# Programmer.net
KiCad netlist of a schematic drawn in Altium Designer
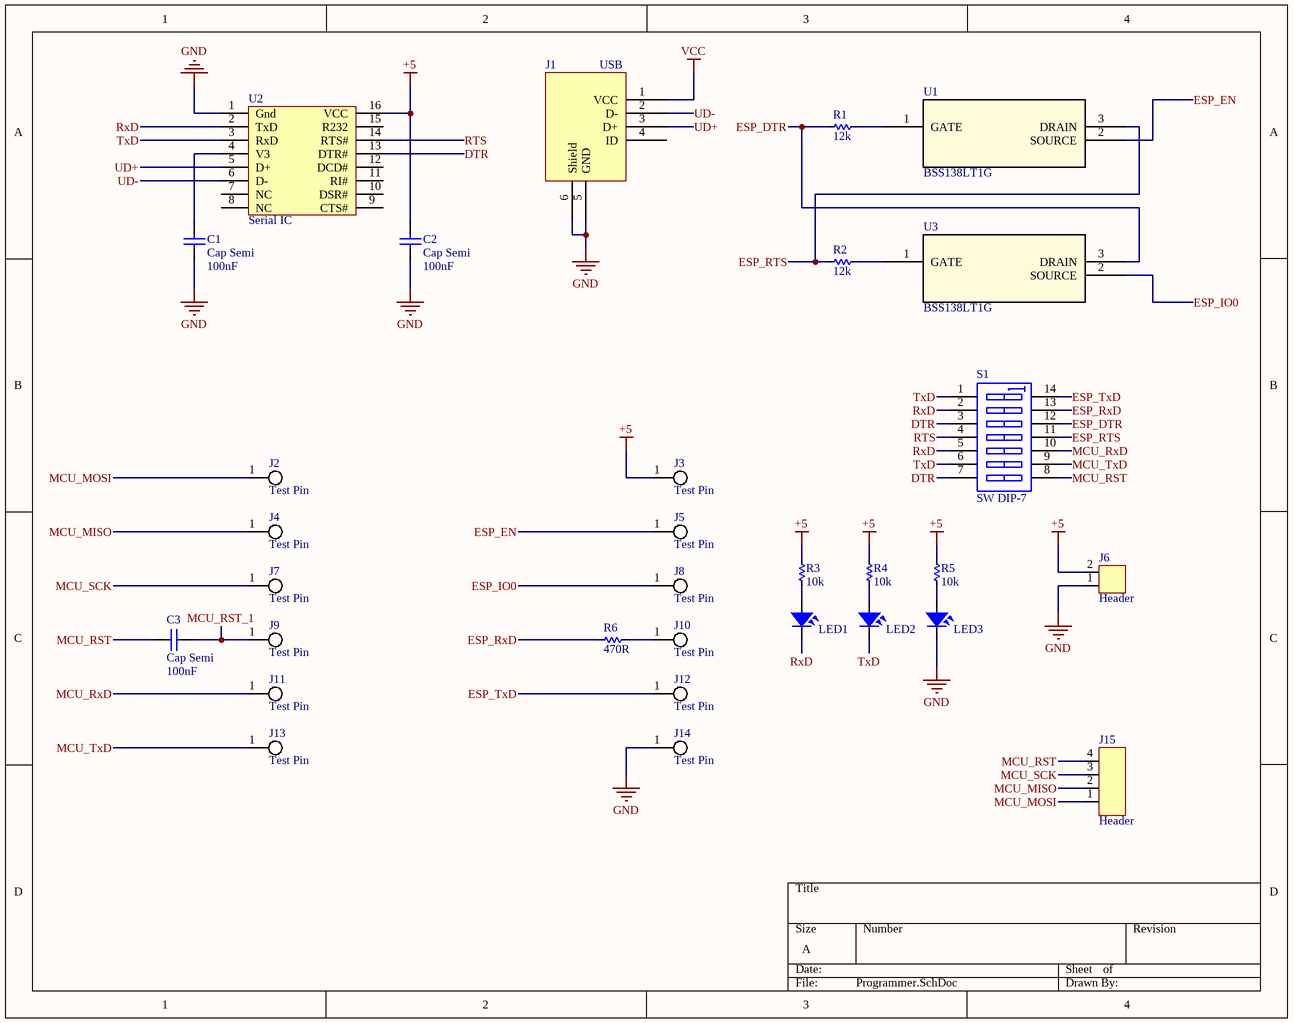
[diagram p0: Programmer.SchDoc]

(export (version "E")
  (design (tool "Eeschema 10.0.6"))
  (components
    (comp (ref "C1")
      (value "Cap Semi")
      (footprint "1608[0603]")
      (description "Capacitor (Semiconductor SIM Model)")
      (fields (field (name "ALTIUM_VALUE") "100nF") (field (name "PUBLISHER") "Altium Limited"))
      (libsource (lib "Miscellaneous Devices") (part "Cap Semi"))
    )
    (comp (ref "C2")
      (value "Cap Semi")
      (footprint "1608[0603]")
      (description "Capacitor (Semiconductor SIM Model)")
      (fields (field (name "ALTIUM_VALUE") "100nF") (field (name "PUBLISHER") "Altium Limited"))
      (libsource (lib "Miscellaneous Devices") (part "Cap Semi"))
    )
    (comp (ref "C3")
      (value "Cap Semi")
      (footprint "1608[0603]")
      (description "Capacitor (Semiconductor SIM Model)")
      (fields (field (name "ALTIUM_VALUE") "100nF") (field (name "PUBLISHER") "Altium Limited"))
      (libsource (lib "Miscellaneous Devices") (part "Cap Semi"))
    )
    (comp (ref "J1")
      (value "USB")
      (footprint "USB-MICRO-B-1")
      (description "MicroUSB 5pin TypeB SMD")
      (libsource (lib "MyLibrary-001") (part "USB-Micro-B_1"))
    )
    (comp (ref "J2") (value "Test Pin") (footprint "P50-J1") (libsource (lib "TestPin") (part "P50-J1")))
    (comp (ref "J3") (value "Test Pin") (footprint "P50-J1") (libsource (lib "TestPin") (part "P50-J1")))
    (comp (ref "J4") (value "Test Pin") (footprint "P50-J1") (libsource (lib "TestPin") (part "P50-J1")))
    (comp (ref "J5") (value "Test Pin") (footprint "P50-J1") (libsource (lib "TestPin") (part "P50-J1")))
    (comp (ref "J6")
      (value "Header")
      (footprint "Header 1x2 Pin 2.54mm")
      (description "Header 1x2Pin 2.54mm")
      (libsource (lib "MyLibrary-001") (part "Header 1x2Pin 2.54mm"))
    )
    (comp (ref "J7") (value "Test Pin") (footprint "P50-J1") (libsource (lib "TestPin") (part "P50-J1")))
    (comp (ref "J8") (value "Test Pin") (footprint "P50-J1") (libsource (lib "TestPin") (part "P50-J1")))
    (comp (ref "J9") (value "Test Pin") (footprint "P50-J1") (libsource (lib "TestPin") (part "P50-J1")))
    (comp (ref "J10") (value "Test Pin") (footprint "P50-J1") (libsource (lib "TestPin") (part "P50-J1")))
    (comp (ref "J11") (value "Test Pin") (footprint "P50-J1") (libsource (lib "TestPin") (part "P50-J1")))
    (comp (ref "J12") (value "Test Pin") (footprint "P50-J1") (libsource (lib "TestPin") (part "P50-J1")))
    (comp (ref "J13") (value "Test Pin") (footprint "P50-J1") (libsource (lib "TestPin") (part "P50-J1")))
    (comp (ref "J14") (value "Test Pin") (footprint "P50-J1") (libsource (lib "TestPin") (part "P50-J1")))
    (comp (ref "J15")
      (value "Header")
      (footprint "HEADER 1X4PIN 2.54mm")
      (description "Header 1x4Pin 2.54mm")
      (libsource (lib "MyLibrary-001") (part "Header 1x4Pin 2.54mm"))
    )
    (comp (ref "LED1") (value "LED") (footprint "LED-0805-Red") (libsource (lib "LIBRARY") (part "LED SMD")))
    (comp (ref "LED2") (value "LED") (footprint "LED-0805-Red") (libsource (lib "LIBRARY") (part "LED SMD")))
    (comp (ref "LED3") (value "LED") (footprint "LED-0805-Red") (libsource (lib "LIBRARY") (part "LED SMD")))
    (comp (ref "R1")
      (value "12k")
      (footprint "RES-SMD-0603")
      (description "Resistor")
      (fields
        (field (name "MANUFACTURER") "Generic Components")
        (field (name "Comment") "Res")
        (field (name "PUBLISHER") "Altium Hobart Technology Centre")
      )
      (libsource (lib "LIBRARY") (part "Res-SMD"))
    )
    (comp (ref "R2")
      (value "12k")
      (footprint "RES-SMD-0603")
      (description "Resistor")
      (fields
        (field (name "MANUFACTURER") "Generic Components")
        (field (name "Comment") "Res")
        (field (name "PUBLISHER") "Altium Hobart Technology Centre")
      )
      (libsource (lib "LIBRARY") (part "Res-SMD"))
    )
    (comp (ref "R3")
      (value "10k")
      (footprint "RES-SMD-0603")
      (description "Resistor")
      (fields
        (field (name "MANUFACTURER") "Generic Components")
        (field (name "Comment") "Res")
        (field (name "PUBLISHER") "Altium Hobart Technology Centre")
      )
      (libsource (lib "LIBRARY") (part "Res-SMD"))
    )
    (comp (ref "R4")
      (value "10k")
      (footprint "RES-SMD-0603")
      (description "Resistor")
      (fields
        (field (name "MANUFACTURER") "Generic Components")
        (field (name "Comment") "Res")
        (field (name "PUBLISHER") "Altium Hobart Technology Centre")
      )
      (libsource (lib "LIBRARY") (part "Res-SMD"))
    )
    (comp (ref "R5")
      (value "10k")
      (footprint "RES-SMD-0603")
      (description "Resistor")
      (fields
        (field (name "MANUFACTURER") "Generic Components")
        (field (name "Comment") "Res")
        (field (name "PUBLISHER") "Altium Hobart Technology Centre")
      )
      (libsource (lib "LIBRARY") (part "Res-SMD"))
    )
    (comp (ref "R6")
      (value "470R")
      (footprint "RES-SMD-0603")
      (description "Resistor")
      (fields
        (field (name "MANUFACTURER") "Generic Components")
        (field (name "Comment") "Res")
        (field (name "PUBLISHER") "Altium Hobart Technology Centre")
      )
      (libsource (lib "LIBRARY") (part "Res-SMD"))
    )
    (comp (ref "S1")
      (value "SW DIP-7")
      (footprint "DIP-14")
      (description "DIP Switch, 7 Position, SPST")
      (fields (field (name "PUBLISHER") "Altium Limited"))
      (libsource (lib "Miscellaneous Devices") (part "SW DIP-7"))
    )
    (comp (ref "U1")
      (value "BSS138LT1G")
      (footprint "SOT23-3_ONS")
      (description "No Description Available")
      (fields (field (name "COPYRIGHT") "Copyright (C) 2018 Accelerated Designs. All rights reserved"))
      (libsource (lib "BSS138LT1G") (part "BSS138LT1G"))
    )
    (comp (ref "U2")
      (value "Serial IC")
      (footprint "CH340C")
      (description "Transceiver USB 2.0 2Mbps SOP-16_150mil USB ICs RoHS")
      (libsource (lib "CH340C") (part "CH340C"))
    )
    (comp (ref "U3")
      (value "BSS138LT1G")
      (footprint "SOT23-3_ONS")
      (description "No Description Available")
      (fields (field (name "COPYRIGHT") "Copyright (C) 2018 Accelerated Designs. All rights reserved"))
      (libsource (lib "BSS138LT1G") (part "BSS138LT1G"))
    )
  )
  (nets
    (net (code "1") (name "+5") (class "Default")
      (node (ref "C2") (pin "2") (pinfunction "2_2") (pintype "passive"))
      (node (ref "J3") (pin "1") (pinfunction "1_1") (pintype "passive"))
      (node (ref "J6") (pin "2") (pinfunction "2_2") (pintype "passive"))
      (node (ref "R3") (pin "1") (pinfunction "1_1") (pintype "passive"))
      (node (ref "R4") (pin "1") (pinfunction "1_1") (pintype "passive"))
      (node (ref "R5") (pin "1") (pinfunction "1_1") (pintype "passive"))
      (node (ref "U2") (pin "16") (pinfunction "VCC_16") (pintype "passive"))
    )
    (net (code "2") (name "/DTR") (class "Default")
      (node (ref "S1") (pin "3") (pinfunction "A3_3") (pintype "passive"))
      (node (ref "S1") (pin "7") (pinfunction "A7_7") (pintype "passive"))
      (node (ref "U2") (pin "13") (pinfunction "DTR#_13") (pintype "passive"))
    )
    (net (code "3") (name "/ESP_DTR") (class "Default")
      (node (ref "R1") (pin "1") (pinfunction "1_1") (pintype "passive"))
      (node (ref "S1") (pin "12") (pinfunction "B3_12") (pintype "passive"))
      (node (ref "U3") (pin "3") (pinfunction "DRAIN_3") (pintype "passive"))
    )
    (net (code "4") (name "/ESP_EN") (class "Default")
      (node (ref "J5") (pin "1") (pinfunction "1_1") (pintype "passive"))
      (node (ref "U1") (pin "2") (pinfunction "SOURCE_2") (pintype "passive"))
    )
    (net (code "5") (name "/ESP_IO0") (class "Default")
      (node (ref "J8") (pin "1") (pinfunction "1_1") (pintype "passive"))
      (node (ref "U3") (pin "2") (pinfunction "SOURCE_2") (pintype "passive"))
    )
    (net (code "6") (name "/ESP_RTS") (class "Default")
      (node (ref "R2") (pin "1") (pinfunction "1_1") (pintype "passive"))
      (node (ref "S1") (pin "11") (pinfunction "B4_11") (pintype "passive"))
      (node (ref "U1") (pin "3") (pinfunction "DRAIN_3") (pintype "passive"))
    )
    (net (code "7") (name "/ESP_RxD") (class "Default")
      (node (ref "R6") (pin "1") (pinfunction "1_1") (pintype "passive"))
      (node (ref "S1") (pin "13") (pinfunction "B2_13") (pintype "passive"))
    )
    (net (code "8") (name "/ESP_TxD") (class "Default")
      (node (ref "J12") (pin "1") (pinfunction "1_1") (pintype "passive"))
      (node (ref "S1") (pin "14") (pinfunction "B1_14") (pintype "passive"))
    )
    (net (code "9") (name "/MCU_MISO") (class "Default")
      (node (ref "J15") (pin "2") (pinfunction "2_2") (pintype "passive"))
      (node (ref "J4") (pin "1") (pinfunction "1_1") (pintype "passive"))
    )
    (net (code "10") (name "/MCU_MOSI") (class "Default")
      (node (ref "J15") (pin "1") (pinfunction "1_1") (pintype "passive"))
      (node (ref "J2") (pin "1") (pinfunction "1_1") (pintype "passive"))
    )
    (net (code "11") (name "/MCU_RST") (class "Default")
      (node (ref "C3") (pin "2") (pinfunction "2_2") (pintype "passive"))
      (node (ref "J15") (pin "4") (pinfunction "4_4") (pintype "passive"))
      (node (ref "S1") (pin "8") (pinfunction "B7_8") (pintype "passive"))
    )
    (net (code "12") (name "/MCU_RST_1") (class "Default")
      (node (ref "C3") (pin "1") (pinfunction "1_1") (pintype "passive"))
      (node (ref "J9") (pin "1") (pinfunction "1_1") (pintype "passive"))
    )
    (net (code "13") (name "/MCU_RxD") (class "Default")
      (node (ref "J11") (pin "1") (pinfunction "1_1") (pintype "passive"))
      (node (ref "S1") (pin "10") (pinfunction "B5_10") (pintype "passive"))
    )
    (net (code "14") (name "/MCU_SCK") (class "Default")
      (node (ref "J15") (pin "3") (pinfunction "3_3") (pintype "passive"))
      (node (ref "J7") (pin "1") (pinfunction "1_1") (pintype "passive"))
    )
    (net (code "15") (name "/MCU_TxD") (class "Default")
      (node (ref "J13") (pin "1") (pinfunction "1_1") (pintype "passive"))
      (node (ref "S1") (pin "9") (pinfunction "B6_9") (pintype "passive"))
    )
    (net (code "16") (name "/RTS") (class "Default")
      (node (ref "S1") (pin "4") (pinfunction "A4_4") (pintype "passive"))
      (node (ref "U2") (pin "14") (pinfunction "RTS#_14") (pintype "passive"))
    )
    (net (code "17") (name "/RxD") (class "Default")
      (node (ref "LED1") (pin "2") (pinfunction "2_2") (pintype "passive"))
      (node (ref "S1") (pin "2") (pinfunction "A2_2") (pintype "passive"))
      (node (ref "S1") (pin "5") (pinfunction "A5_5") (pintype "passive"))
      (node (ref "U2") (pin "2") (pinfunction "TxD_2") (pintype "passive"))
    )
    (net (code "18") (name "/TxD") (class "Default")
      (node (ref "LED2") (pin "2") (pinfunction "2_2") (pintype "passive"))
      (node (ref "S1") (pin "1") (pinfunction "A1_1") (pintype "passive"))
      (node (ref "S1") (pin "6") (pinfunction "A6_6") (pintype "passive"))
      (node (ref "U2") (pin "3") (pinfunction "RxD_3") (pintype "passive"))
    )
    (net (code "19") (name "/UD+") (class "Default")
      (node (ref "J1") (pin "3") (pinfunction "D+_3") (pintype "passive"))
      (node (ref "U2") (pin "5") (pinfunction "D+_5") (pintype "passive"))
    )
    (net (code "20") (name "/UD-") (class "Default")
      (node (ref "J1") (pin "2") (pinfunction "D-_2") (pintype "passive"))
      (node (ref "U2") (pin "6") (pinfunction "D-_6") (pintype "passive"))
    )
    (net (code "21") (name "GND") (class "Default")
      (node (ref "C1") (pin "1") (pinfunction "1_1") (pintype "passive"))
      (node (ref "C2") (pin "1") (pinfunction "1_1") (pintype "passive"))
      (node (ref "J1") (pin "5") (pinfunction "GND_5") (pintype "passive"))
      (node (ref "J1") (pin "6") (pinfunction "Shield_6") (pintype "passive"))
      (node (ref "J14") (pin "1") (pinfunction "1_1") (pintype "passive"))
      (node (ref "J6") (pin "1") (pinfunction "1_1") (pintype "passive"))
      (node (ref "LED3") (pin "2") (pinfunction "2_2") (pintype "passive"))
      (node (ref "U2") (pin "1") (pinfunction "Gnd_1") (pintype "passive"))
    )
    (net (code "22") (name "Net-(J10-Pad1)") (class "Default")
      (node (ref "J10") (pin "1") (pinfunction "1_1") (pintype "passive"))
      (node (ref "R6") (pin "2") (pinfunction "2_2") (pintype "passive"))
    )
    (net (code "23") (name "Net-(LED1-Pad1)") (class "Default")
      (node (ref "LED1") (pin "1") (pinfunction "1_1") (pintype "passive"))
      (node (ref "R3") (pin "2") (pinfunction "2_2") (pintype "passive"))
    )
    (net (code "24") (name "Net-(LED2-Pad1)") (class "Default")
      (node (ref "LED2") (pin "1") (pinfunction "1_1") (pintype "passive"))
      (node (ref "R4") (pin "2") (pinfunction "2_2") (pintype "passive"))
    )
    (net (code "25") (name "Net-(LED3-Pad1)") (class "Default")
      (node (ref "LED3") (pin "1") (pinfunction "1_1") (pintype "passive"))
      (node (ref "R5") (pin "2") (pinfunction "2_2") (pintype "passive"))
    )
    (net (code "26") (name "Net-(U1-GATE)") (class "Default")
      (node (ref "R1") (pin "2") (pinfunction "2_2") (pintype "passive"))
      (node (ref "U1") (pin "1") (pinfunction "GATE_1") (pintype "passive"))
    )
    (net (code "27") (name "Net-(U2-V3)") (class "Default")
      (node (ref "C1") (pin "2") (pinfunction "2_2") (pintype "passive"))
      (node (ref "U2") (pin "4") (pinfunction "V3_4") (pintype "passive"))
    )
    (net (code "28") (name "Net-(U3-GATE)") (class "Default")
      (node (ref "R2") (pin "2") (pinfunction "2_2") (pintype "passive"))
      (node (ref "U3") (pin "1") (pinfunction "GATE_1") (pintype "passive"))
    )
    (net (code "29") (name "VCC") (class "Default")
      (node (ref "J1") (pin "1") (pinfunction "VCC_1") (pintype "passive"))
    )
    (net (code "30") (name "unconnected-(J1-ID-Pad4)") (class "Default")
      (node (ref "J1") (pin "4") (pinfunction "ID_4") (pintype "passive"))
    )
    (net (code "31") (name "unconnected-(U2-CTS#-Pad9)") (class "Default")
      (node (ref "U2") (pin "9") (pinfunction "CTS#_9") (pintype "passive"))
    )
    (net (code "32") (name "unconnected-(U2-DCD#-Pad12)") (class "Default")
      (node (ref "U2") (pin "12") (pinfunction "DCD#_12") (pintype "passive"))
    )
    (net (code "33") (name "unconnected-(U2-DSR#-Pad10)") (class "Default")
      (node (ref "U2") (pin "10") (pinfunction "DSR#_10") (pintype "passive"))
    )
    (net (code "34") (name "unconnected-(U2-NC-Pad7)") (class "Default")
      (node (ref "U2") (pin "7") (pinfunction "NC_7") (pintype "passive"))
    )
    (net (code "35") (name "unconnected-(U2-NC-Pad8)") (class "Default")
      (node (ref "U2") (pin "8") (pinfunction "NC_8") (pintype "passive"))
    )
    (net (code "36") (name "unconnected-(U2-R232-Pad15)") (class "Default")
      (node (ref "U2") (pin "15") (pinfunction "R232_15") (pintype "passive"))
    )
    (net (code "37") (name "unconnected-(U2-RI#-Pad11)") (class "Default")
      (node (ref "U2") (pin "11") (pinfunction "RI#_11") (pintype "passive"))
    )
  )
)
